# NFC_BusinessCard.net
KiCad netlist of a schematic drawn in EAGLE
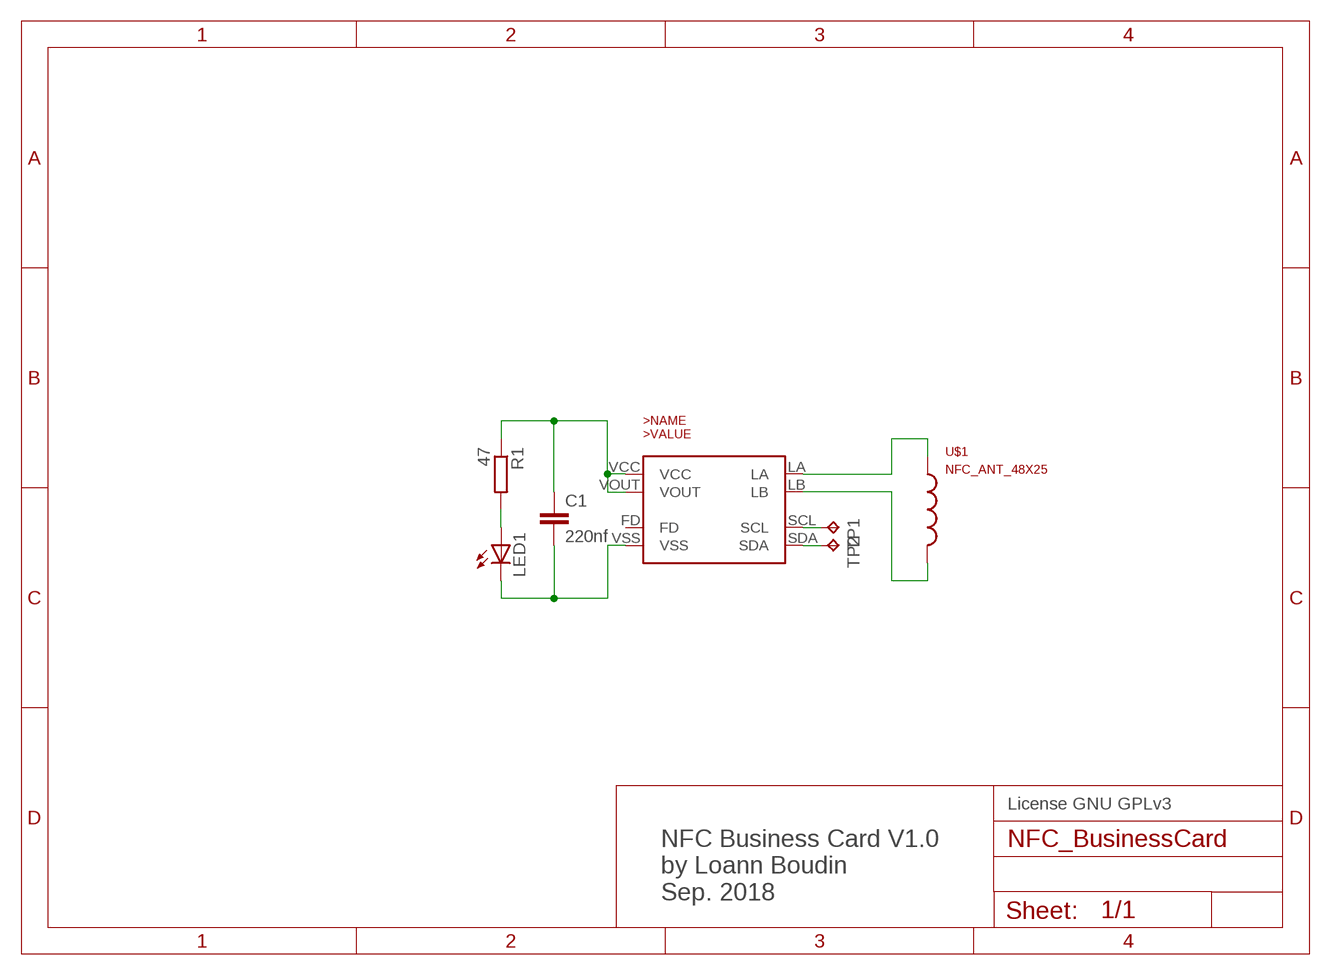
[diagram p0: schematic, sheet 1]

(export (version "E")
  (design (tool "Eeschema 10.0.6"))
  (components
    (comp (ref "C1")
      (value "220nf")
      (footprint "eagle-import:C0603")
      (libsource (lib "eagle-import") (part "C-EUC0603"))
    )
    (comp (ref "LED1")
      (value "LEDSML0805")
      (footprint "eagle-import:SML0805")
      (libsource (lib "eagle-import") (part "LEDSML0805"))
    )
    (comp (ref "NT3H1101")
      (value "NT3H1101")
      (footprint "eagle-import:XQFN8")
      (libsource (lib "eagle-import") (part "NT3H1101"))
    )
    (comp (ref "R1")
      (value "47")
      (footprint "eagle-import:R0603")
      (libsource (lib "eagle-import") (part "R-EU_R0603"))
    )
    (comp (ref "TP1")
      (value "TPTP06R")
      (footprint "eagle-import:TP06R")
      (libsource (lib "eagle-import") (part "TPTP06R"))
    )
    (comp (ref "TP2")
      (value "TPTP06R")
      (footprint "eagle-import:TP06R")
      (libsource (lib "eagle-import") (part "TPTP06R"))
    )
    (comp (ref "U$1")
      (value "NFC_ANT_48X25")
      (footprint "eagle-import:NFC_ANT_48X25")
      (libsource (lib "eagle-import") (part "NFC_ANT_48X25"))
    )
  )
  (nets
    (net (code "1") (name "Net-(C1-Pad1)") (class "Default")
      (node (ref "C1") (pin "1") (pinfunction "1_1") (pintype "passive"))
      (node (ref "NT3H1101") (pin "VCC") (pinfunction "VCC_VCC") (pintype "bidirectional"))
      (node (ref "NT3H1101") (pin "VOUT") (pinfunction "VOUT_VOUT") (pintype "bidirectional"))
      (node (ref "R1") (pin "1") (pinfunction "1_1") (pintype "passive"))
    )
    (net (code "2") (name "Net-(C1-Pad2)") (class "Default")
      (node (ref "C1") (pin "2") (pinfunction "2_2") (pintype "passive"))
      (node (ref "LED1") (pin "C") (pinfunction "C_C") (pintype "passive"))
      (node (ref "NT3H1101") (pin "VSS") (pinfunction "VSS_VSS") (pintype "bidirectional"))
    )
    (net (code "3") (name "Net-(LED1-PadA)") (class "Default")
      (node (ref "LED1") (pin "A") (pinfunction "A_A") (pintype "passive"))
      (node (ref "R1") (pin "2") (pinfunction "2_2") (pintype "passive"))
    )
    (net (code "4") (name "Net-(NT3H1101-PadLA)") (class "Default")
      (node (ref "NT3H1101") (pin "LA") (pinfunction "LA_LA") (pintype "bidirectional"))
      (node (ref "U$1") (pin "A") (pinfunction "A_A") (pintype "bidirectional"))
    )
    (net (code "5") (name "Net-(NT3H1101-PadLB)") (class "Default")
      (node (ref "NT3H1101") (pin "LB") (pinfunction "LB_LB") (pintype "bidirectional"))
      (node (ref "U$1") (pin "B") (pinfunction "B_B") (pintype "bidirectional"))
      (node (ref "U$1") (pin "P$3") (pinfunction "B_P$3") (pintype "bidirectional"))
    )
    (net (code "6") (name "Net-(NT3H1101-PadSCL)") (class "Default")
      (node (ref "NT3H1101") (pin "SCL") (pinfunction "SCL_SCL") (pintype "bidirectional"))
      (node (ref "TP1") (pin "TP") (pinfunction "TP_TP") (pintype "input"))
    )
    (net (code "7") (name "Net-(NT3H1101-PadSDA)") (class "Default")
      (node (ref "NT3H1101") (pin "SDA") (pinfunction "SDA_SDA") (pintype "bidirectional"))
      (node (ref "TP2") (pin "TP") (pinfunction "TP_TP") (pintype "input"))
    )
    (net (code "8") (name "unconnected-(NT3H1101-PadFD)") (class "Default")
      (node (ref "NT3H1101") (pin "FD") (pinfunction "FD_FD") (pintype "bidirectional"))
    )
  )
)
